# LTC2949.net
KiCad netlist of a schematic drawn in Altium Designer
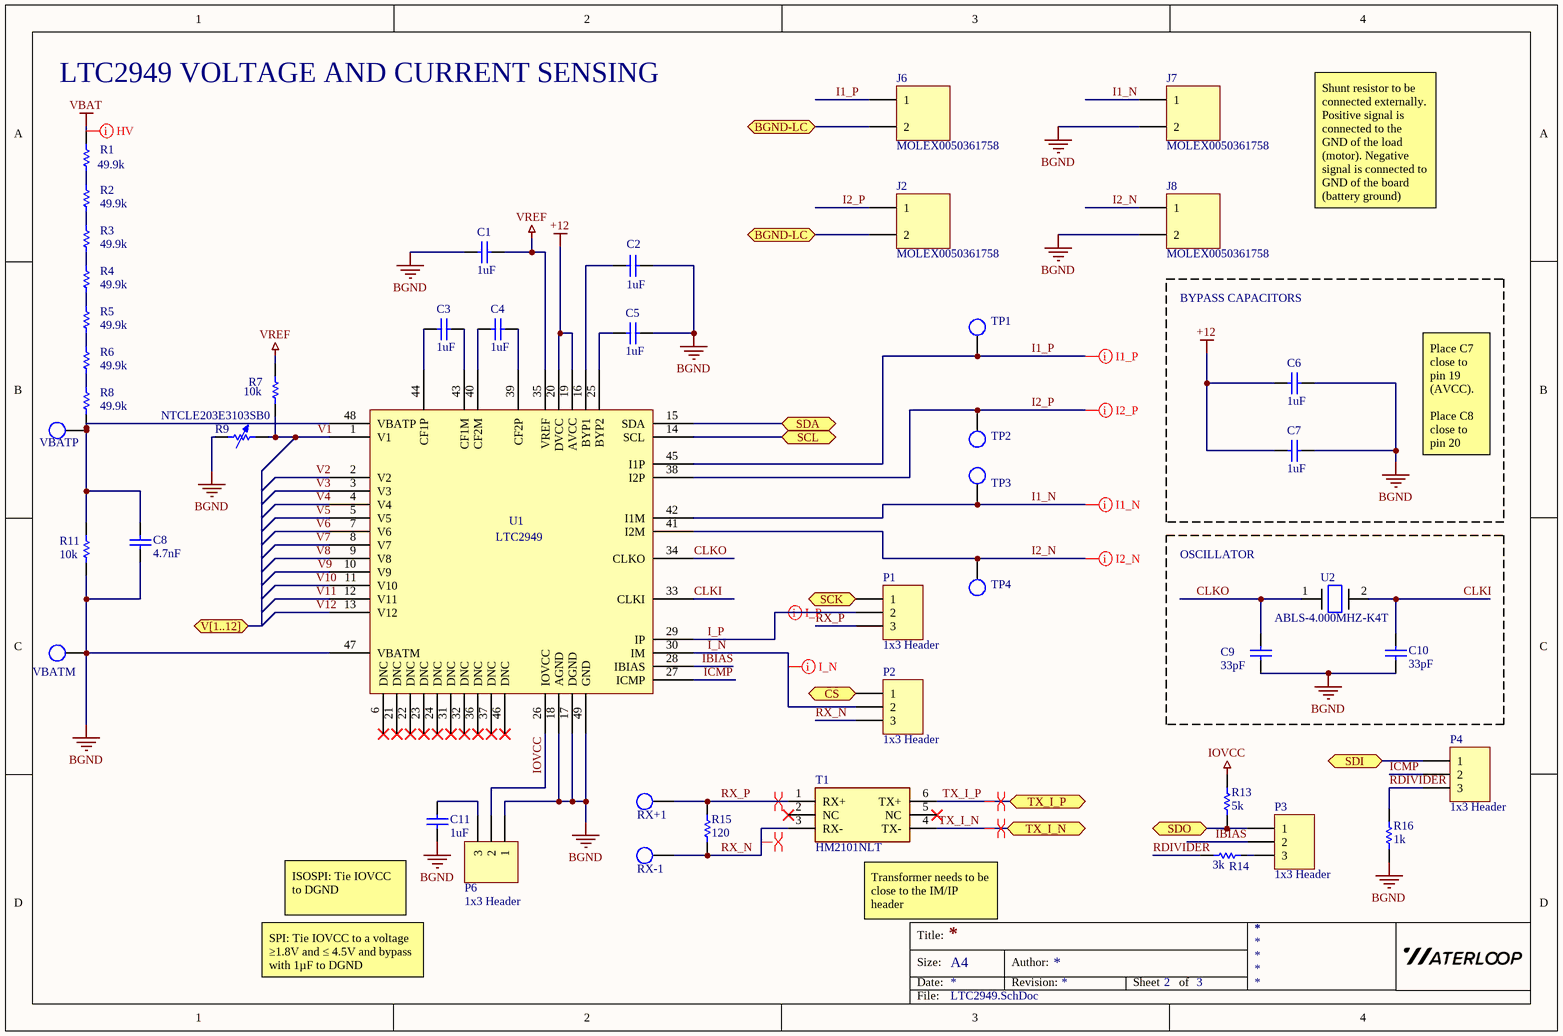
[diagram p0: LTC2949.SchDoc]

(export (version "E")
  (design (tool "Eeschema 10.0.6"))
  (components
    (comp (ref "C1")
      (value "1uF")
      (footprint "0805 - Capacitor")
      (description "Nonpolarized Capacitor")
      (fields (field (name "Comment") "Capacitor - Nonpolarized"))
      (libsource (lib "General") (part "Capacitor - Nonpolarized"))
    )
    (comp (ref "C2")
      (value "1uF")
      (footprint "0805 - Capacitor")
      (description "Nonpolarized Capacitor")
      (libsource (lib "General") (part "Capacitor - Nonpolarized"))
    )
    (comp (ref "C3")
      (value "1uF")
      (footprint "0805 - Capacitor")
      (description "Nonpolarized Capacitor")
      (libsource (lib "General") (part "Capacitor - Nonpolarized"))
    )
    (comp (ref "C4")
      (value "1uF")
      (footprint "0805 - Capacitor")
      (description "Nonpolarized Capacitor")
      (libsource (lib "General") (part "Capacitor - Nonpolarized"))
    )
    (comp (ref "C5")
      (value "1uF")
      (footprint "0805 - Capacitor")
      (description "Nonpolarized Capacitor")
      (libsource (lib "General") (part "Capacitor - Nonpolarized"))
    )
    (comp (ref "C6")
      (value "1uF")
      (footprint "0805 - Capacitor")
      (description "Nonpolarized Capacitor")
      (libsource (lib "General") (part "Capacitor - Nonpolarized"))
    )
    (comp (ref "C7")
      (value "1uF")
      (footprint "0805 - Capacitor")
      (description "Nonpolarized Capacitor")
      (libsource (lib "General") (part "Capacitor - Nonpolarized"))
    )
    (comp (ref "C8")
      (value "4.7nF")
      (footprint "0805 - Capacitor")
      (description "Nonpolarized Capacitor")
      (libsource (lib "General") (part "Capacitor - Nonpolarized"))
    )
    (comp (ref "C9")
      (value "33pF")
      (footprint "0805 - Capacitor")
      (description "Nonpolarized Capacitor")
      (libsource (lib "General") (part "Capacitor - Nonpolarized"))
    )
    (comp (ref "C10")
      (value "33pF")
      (footprint "0805 - Capacitor")
      (description "Nonpolarized Capacitor")
      (libsource (lib "General") (part "Capacitor - Nonpolarized"))
    )
    (comp (ref "C11")
      (value "1uF")
      (footprint "0805 - Capacitor")
      (description "Nonpolarized Capacitor")
      (libsource (lib "General") (part "Capacitor - Nonpolarized"))
    )
    (comp (ref "J2")
      (value "MOLEX0050361758")
      (footprint "Molex0050361758")
      (description "Connector Header Through Hole, Right Angle 2 position -")
      (fields (field (name "MANUFACTURER") "Molex") (field (name "MANUFACTURER PART NUMBER") "0050361758"))
      (libsource (lib "GeneralConnectors") (part "MOLEX0050361758"))
    )
    (comp (ref "J6")
      (value "MOLEX0050361758")
      (footprint "Molex0050361758")
      (description "Connector Header Through Hole, Right Angle 2 position -")
      (fields (field (name "MANUFACTURER") "Molex") (field (name "MANUFACTURER PART NUMBER") "0050361758"))
      (libsource (lib "GeneralConnectors") (part "MOLEX0050361758"))
    )
    (comp (ref "J7")
      (value "MOLEX0050361758")
      (footprint "Molex0050361758")
      (description "Connector Header Through Hole, Right Angle 2 position -")
      (fields (field (name "MANUFACTURER") "Molex") (field (name "MANUFACTURER PART NUMBER") "0050361758"))
      (libsource (lib "GeneralConnectors") (part "MOLEX0050361758"))
    )
    (comp (ref "J8")
      (value "MOLEX0050361758")
      (footprint "Molex0050361758")
      (description "Connector Header Through Hole, Right Angle 2 position -")
      (fields (field (name "MANUFACTURER") "Molex") (field (name "MANUFACTURER PART NUMBER") "0050361758"))
      (libsource (lib "GeneralConnectors") (part "MOLEX0050361758"))
    )
    (comp (ref "P1")
      (value "1x3 Header")
      (footprint "HDR1X3")
      (description "1x3 Pin Header")
      (libsource (lib "GeneralConnectors") (part "1x3 Header"))
    )
    (comp (ref "P2")
      (value "1x3 Header")
      (footprint "HDR1X3")
      (description "1x3 Pin Header")
      (libsource (lib "GeneralConnectors") (part "1x3 Header"))
    )
    (comp (ref "P3")
      (value "1x3 Header")
      (footprint "HDR1X3")
      (description "1x3 Pin Header")
      (libsource (lib "GeneralConnectors") (part "1x3 Header"))
    )
    (comp (ref "P4")
      (value "1x3 Header")
      (footprint "HDR1X3")
      (description "1x3 Pin Header")
      (libsource (lib "GeneralConnectors") (part "1x3 Header"))
    )
    (comp (ref "P6")
      (value "1x3 Header")
      (footprint "HDR1X3")
      (description "1x3 Pin Header")
      (libsource (lib "") (part "1x3 Header_1"))
    )
    (comp (ref "R1")
      (value "49.9k")
      (footprint "1206 - Resistor")
      (description "Resistor")
      (libsource (lib "General") (part "Resistor"))
    )
    (comp (ref "R2")
      (value "49.9k")
      (footprint "1206 - Resistor")
      (description "Resistor")
      (libsource (lib "General") (part "Resistor"))
    )
    (comp (ref "R3")
      (value "49.9k")
      (footprint "1206 - Resistor")
      (description "Resistor")
      (libsource (lib "General") (part "Resistor"))
    )
    (comp (ref "R4")
      (value "49.9k")
      (footprint "1206 - Resistor")
      (description "Resistor")
      (libsource (lib "General") (part "Resistor"))
    )
    (comp (ref "R5")
      (value "49.9k")
      (footprint "1206 - Resistor")
      (description "Resistor")
      (libsource (lib "General") (part "Resistor"))
    )
    (comp (ref "R6")
      (value "49.9k")
      (footprint "1206 - Resistor")
      (description "Resistor")
      (libsource (lib "General") (part "Resistor"))
    )
    (comp (ref "R7")
      (value "10k")
      (footprint "0603 - Resistor")
      (description "Resistor")
      (libsource (lib "General") (part "Resistor"))
    )
    (comp (ref "R8")
      (value "49.9k")
      (footprint "1206 - Resistor")
      (description "Resistor")
      (libsource (lib "General") (part "Resistor"))
    )
    (comp (ref "R9")
      (value "Resistor - Variable")
      (footprint "0603 - Resistor")
      (description "Variable Resistor")
      (libsource (lib "General") (part "Resistor - Variable"))
    )
    (comp (ref "R11")
      (value "10k")
      (footprint "0603 - Resistor")
      (description "Resistor")
      (libsource (lib "General") (part "Resistor"))
    )
    (comp (ref "R13")
      (value "5k")
      (footprint "0603 - Resistor")
      (description "Resistor")
      (libsource (lib "General") (part "Resistor"))
    )
    (comp (ref "R14")
      (value "3k")
      (footprint "0603 - Resistor")
      (description "Resistor")
      (libsource (lib "General") (part "Resistor"))
    )
    (comp (ref "R15")
      (value "120")
      (footprint "0603 - Resistor")
      (description "Resistor")
      (libsource (lib "General") (part "Resistor"))
    )
    (comp (ref "R16")
      (value "1k")
      (footprint "0603 - Resistor")
      (description "Resistor")
      (libsource (lib "General") (part "Resistor"))
    )
    (comp (ref "RX+1")
      (value "Test Point")
      (footprint "Test Point - 5002")
      (libsource (lib "General") (part "Test Point"))
    )
    (comp (ref "RX-1")
      (value "Test Point")
      (footprint "Test Point - 5002")
      (libsource (lib "General") (part "Test Point"))
    )
    (comp (ref "T1")
      (value "HM2101NLT")
      (footprint "HM2101NLT")
      (description "Pulse Transformer 1:1 Surface Mount 150µH, 450µH")
      (libsource (lib "GeneralComponents") (part "HM2101NLT"))
    )
    (comp (ref "TP1")
      (value "Test Point")
      (footprint "Test Point - 5002")
      (libsource (lib "General") (part "Test Point"))
    )
    (comp (ref "TP2")
      (value "Test Point")
      (footprint "Test Point - 5002")
      (libsource (lib "General") (part "Test Point"))
    )
    (comp (ref "TP3")
      (value "Test Point")
      (footprint "Test Point - 5002")
      (libsource (lib "General") (part "Test Point"))
    )
    (comp (ref "TP4")
      (value "Test Point")
      (footprint "Test Point - 5002")
      (libsource (lib "General") (part "Test Point"))
    )
    (comp (ref "U1")
      (value "LTC2949")
      (footprint "LTC2949")
      (fields
        (field (name "MANUFACTURER") "Analog Devices")
        (field (name "MANUFACTURER PART NUMBER") "LTC2949ILXE#3ZZPBF")
      )
      (libsource (lib "BMS") (part "LTC2949"))
    )
    (comp (ref "U2")
      (value "ABLS-4.000MHZ-K4T")
      (footprint "ABLS_4MHZ-K4T")
      (description "Crystal Oscillator 4MHz 18pF")
      (libsource (lib "BMS") (part "ABLS-4.000MHZ-K4T"))
    )
    (comp (ref "VBATM")
      (value "Test Point")
      (footprint "Test Point - 5002")
      (libsource (lib "General") (part "Test Point"))
    )
    (comp (ref "VBATP")
      (value "Test Point")
      (footprint "Test Point - 5002")
      (libsource (lib "General") (part "Test Point"))
    )
  )
  (nets
    (net (code "1") (name "+12") (class "Default")
      (node (ref "C6") (pin "1") (pinfunction "1_1") (pintype "passive"))
      (node (ref "C7") (pin "1") (pinfunction "1_1") (pintype "passive"))
      (node (ref "U1") (pin "19") (pinfunction "AVCC_19") (pintype "power_in"))
      (node (ref "U1") (pin "20") (pinfunction "DVCC_20") (pintype "power_in"))
    )
    (net (code "3") (name "/BGND-LC") (class "Default")
      (node (ref "J2") (pin "2") (pinfunction "2_2") (pintype "passive"))
      (node (ref "J6") (pin "2") (pinfunction "2_2") (pintype "passive"))
    )
    (net (code "4") (name "/CLKI") (class "Default")
      (node (ref "C10") (pin "2") (pinfunction "2_2") (pintype "passive"))
      (node (ref "U1") (pin "33") (pinfunction "CLKI_33") (pintype "passive"))
      (node (ref "U2") (pin "2") (pinfunction "2_2") (pintype "passive"))
    )
    (net (code "5") (name "/CLKO") (class "Default")
      (node (ref "C9") (pin "2") (pinfunction "2_2") (pintype "passive"))
      (node (ref "U1") (pin "34") (pinfunction "CLKO_34") (pintype "passive"))
      (node (ref "U2") (pin "1") (pinfunction "1_1") (pintype "passive"))
    )
    (net (code "6") (name "/CS") (class "Default")
      (node (ref "P2") (pin "1") (pinfunction "1_1") (pintype "passive"))
    )
    (net (code "7") (name "/I1_N") (class "Default")
      (node (ref "J7") (pin "1") (pinfunction "1_1") (pintype "passive"))
      (node (ref "TP3") (pin "1") (pinfunction "0_1") (pintype "passive"))
      (node (ref "U1") (pin "42") (pinfunction "I1M_42") (pintype "passive"))
    )
    (net (code "8") (name "/I1_P") (class "Default")
      (node (ref "J6") (pin "1") (pinfunction "1_1") (pintype "passive"))
      (node (ref "TP1") (pin "1") (pinfunction "0_1") (pintype "passive"))
      (node (ref "U1") (pin "45") (pinfunction "I1P_45") (pintype "passive"))
    )
    (net (code "9") (name "/I2_N") (class "Default")
      (node (ref "J8") (pin "1") (pinfunction "1_1") (pintype "passive"))
      (node (ref "TP4") (pin "1") (pinfunction "0_1") (pintype "passive"))
      (node (ref "U1") (pin "41") (pinfunction "I2M_41") (pintype "passive"))
    )
    (net (code "10") (name "/I2_P") (class "Default")
      (node (ref "J2") (pin "1") (pinfunction "1_1") (pintype "passive"))
      (node (ref "TP2") (pin "1") (pinfunction "0_1") (pintype "passive"))
      (node (ref "U1") (pin "38") (pinfunction "I2P_38") (pintype "passive"))
    )
    (net (code "11") (name "/IBIAS") (class "Default")
      (node (ref "P3") (pin "2") (pinfunction "2_2") (pintype "passive"))
      (node (ref "U1") (pin "28") (pinfunction "IBIAS_28") (pintype "passive"))
    )
    (net (code "12") (name "/ICMP") (class "Default")
      (node (ref "P4") (pin "2") (pinfunction "2_2") (pintype "passive"))
      (node (ref "U1") (pin "27") (pinfunction "ICMP_27") (pintype "passive"))
    )
    (net (code "13") (name "/I_N") (class "Default")
      (node (ref "P2") (pin "2") (pinfunction "2_2") (pintype "passive"))
      (node (ref "U1") (pin "30") (pinfunction "IM_30") (pintype "passive"))
    )
    (net (code "14") (name "/I_P") (class "Default")
      (node (ref "P1") (pin "2") (pinfunction "2_2") (pintype "passive"))
      (node (ref "U1") (pin "29") (pinfunction "IP_29") (pintype "passive"))
    )
    (net (code "15") (name "/RDIVIDER") (class "Default")
      (node (ref "P4") (pin "3") (pinfunction "3_3") (pintype "passive"))
      (node (ref "R14") (pin "1") (pinfunction "1_1") (pintype "passive"))
      (node (ref "R16") (pin "1") (pinfunction "1_1") (pintype "passive"))
    )
    (net (code "16") (name "/RX_N") (class "Default")
      (node (ref "P2") (pin "3") (pinfunction "3_3") (pintype "passive"))
      (node (ref "R15") (pin "1") (pinfunction "1_1") (pintype "passive"))
      (node (ref "RX-1") (pin "1") (pinfunction "0_1") (pintype "passive"))
      (node (ref "T1") (pin "3") (pinfunction "RX-_3") (pintype "passive"))
    )
    (net (code "17") (name "/RX_P") (class "Default")
      (node (ref "P1") (pin "3") (pinfunction "3_3") (pintype "passive"))
      (node (ref "R15") (pin "2") (pinfunction "2_2") (pintype "passive"))
      (node (ref "RX+1") (pin "1") (pinfunction "0_1") (pintype "passive"))
      (node (ref "T1") (pin "1") (pinfunction "RX+_1") (pintype "passive"))
    )
    (net (code "18") (name "/SCK") (class "Default")
      (node (ref "P1") (pin "1") (pinfunction "1_1") (pintype "passive"))
    )
    (net (code "19") (name "/SCL") (class "Default")
      (node (ref "U1") (pin "14") (pinfunction "SCL_14") (pintype "passive"))
    )
    (net (code "20") (name "/SDA") (class "Default")
      (node (ref "U1") (pin "15") (pinfunction "SDA_15") (pintype "passive"))
    )
    (net (code "21") (name "/SDI") (class "Default")
      (node (ref "P4") (pin "1") (pinfunction "1_1") (pintype "passive"))
    )
    (net (code "22") (name "/SDO") (class "Default")
      (node (ref "P3") (pin "1") (pinfunction "1_1") (pintype "passive"))
      (node (ref "R13") (pin "1") (pinfunction "1_1") (pintype "passive"))
    )
    (net (code "23") (name "/TX_I_N") (class "Default")
      (node (ref "T1") (pin "4") (pinfunction "TX-_4") (pintype "passive"))
    )
    (net (code "24") (name "/TX_I_P") (class "Default")
      (node (ref "T1") (pin "6") (pinfunction "TX+_6") (pintype "passive"))
    )
    (net (code "25") (name "/V1") (class "Default")
      (node (ref "R7") (pin "1") (pinfunction "1_1") (pintype "passive"))
      (node (ref "R9") (pin "2") (pinfunction "2_2") (pintype "passive"))
      (node (ref "U1") (pin "1") (pinfunction "V1_1") (pintype "passive"))
    )
    (net (code "26") (name "/V2") (class "Default")
      (node (ref "U1") (pin "2") (pinfunction "V2_2") (pintype "passive"))
    )
    (net (code "27") (name "/V3") (class "Default")
      (node (ref "U1") (pin "3") (pinfunction "V3_3") (pintype "passive"))
    )
    (net (code "28") (name "/V4") (class "Default")
      (node (ref "U1") (pin "4") (pinfunction "V4_4") (pintype "passive"))
    )
    (net (code "29") (name "/V5") (class "Default")
      (node (ref "U1") (pin "5") (pinfunction "V5_5") (pintype "passive"))
    )
    (net (code "30") (name "/V6") (class "Default")
      (node (ref "U1") (pin "7") (pinfunction "V6_7") (pintype "passive"))
    )
    (net (code "31") (name "/V7") (class "Default")
      (node (ref "U1") (pin "8") (pinfunction "V7_8") (pintype "passive"))
    )
    (net (code "32") (name "/V8") (class "Default")
      (node (ref "U1") (pin "9") (pinfunction "V8_9") (pintype "passive"))
    )
    (net (code "33") (name "/V9") (class "Default")
      (node (ref "U1") (pin "10") (pinfunction "V9_10") (pintype "passive"))
    )
    (net (code "34") (name "/V10") (class "Default")
      (node (ref "U1") (pin "11") (pinfunction "V10_11") (pintype "passive"))
    )
    (net (code "35") (name "/V11") (class "Default")
      (node (ref "U1") (pin "12") (pinfunction "V11_12") (pintype "passive"))
    )
    (net (code "36") (name "/V12") (class "Default")
      (node (ref "U1") (pin "13") (pinfunction "V12_13") (pintype "passive"))
    )
    (net (code "38") (name "BGND") (class "Default")
      (node (ref "C1") (pin "1") (pinfunction "1_1") (pintype "passive"))
      (node (ref "C10") (pin "1") (pinfunction "1_1") (pintype "passive"))
      (node (ref "C11") (pin "1") (pinfunction "1_1") (pintype "passive"))
      (node (ref "C2") (pin "2") (pinfunction "2_2") (pintype "passive"))
      (node (ref "C5") (pin "2") (pinfunction "2_2") (pintype "passive"))
      (node (ref "C6") (pin "2") (pinfunction "2_2") (pintype "passive"))
      (node (ref "C7") (pin "2") (pinfunction "2_2") (pintype "passive"))
      (node (ref "C8") (pin "1") (pinfunction "1_1") (pintype "passive"))
      (node (ref "C9") (pin "1") (pinfunction "1_1") (pintype "passive"))
      (node (ref "J7") (pin "2") (pinfunction "2_2") (pintype "passive"))
      (node (ref "J8") (pin "2") (pinfunction "2_2") (pintype "passive"))
      (node (ref "P6") (pin "1") (pinfunction "1_1") (pintype "passive"))
      (node (ref "R11") (pin "1") (pinfunction "1_1") (pintype "passive"))
      (node (ref "R16") (pin "2") (pinfunction "2_2") (pintype "passive"))
      (node (ref "R9") (pin "1") (pinfunction "1_1") (pintype "passive"))
      (node (ref "U1") (pin "17") (pinfunction "DGND_17") (pintype "power_in"))
      (node (ref "U1") (pin "18") (pinfunction "AGND_18") (pintype "power_in"))
      (node (ref "U1") (pin "47") (pinfunction "VBATM_47") (pintype "passive"))
      (node (ref "U1") (pin "49") (pinfunction "GND_49") (pintype "power_in"))
      (node (ref "VBATM") (pin "1") (pinfunction "0_1") (pintype "passive"))
    )
    (net (code "39") (name "IOVCC") (class "Default")
      (node (ref "P6") (pin "2") (pinfunction "2_2") (pintype "passive"))
      (node (ref "R13") (pin "2") (pinfunction "2_2") (pintype "passive"))
      (node (ref "U1") (pin "26") (pinfunction "IOVCC_26") (pintype "power_in"))
    )
    (net (code "40") (name "Net-(C11-Pad2)") (class "Default")
      (node (ref "C11") (pin "2") (pinfunction "2_2") (pintype "passive"))
      (node (ref "P6") (pin "3") (pinfunction "3_3") (pintype "passive"))
    )
    (net (code "41") (name "Net-(P3-Pad3)") (class "Default")
      (node (ref "P3") (pin "3") (pinfunction "3_3") (pintype "passive"))
      (node (ref "R14") (pin "2") (pinfunction "2_2") (pintype "passive"))
    )
    (net (code "42") (name "Net-(R1-Pad1)") (class "Default")
      (node (ref "R1") (pin "1") (pinfunction "1_1") (pintype "passive"))
      (node (ref "R2") (pin "2") (pinfunction "2_2") (pintype "passive"))
    )
    (net (code "43") (name "Net-(R2-Pad1)") (class "Default")
      (node (ref "R2") (pin "1") (pinfunction "1_1") (pintype "passive"))
      (node (ref "R3") (pin "2") (pinfunction "2_2") (pintype "passive"))
    )
    (net (code "44") (name "Net-(R3-Pad1)") (class "Default")
      (node (ref "R3") (pin "1") (pinfunction "1_1") (pintype "passive"))
      (node (ref "R4") (pin "2") (pinfunction "2_2") (pintype "passive"))
    )
    (net (code "45") (name "Net-(R4-Pad1)") (class "Default")
      (node (ref "R4") (pin "1") (pinfunction "1_1") (pintype "passive"))
      (node (ref "R5") (pin "2") (pinfunction "2_2") (pintype "passive"))
    )
    (net (code "46") (name "Net-(R5-Pad1)") (class "Default")
      (node (ref "R5") (pin "1") (pinfunction "1_1") (pintype "passive"))
      (node (ref "R6") (pin "2") (pinfunction "2_2") (pintype "passive"))
    )
    (net (code "47") (name "Net-(R6-Pad1)") (class "Default")
      (node (ref "R6") (pin "1") (pinfunction "1_1") (pintype "passive"))
      (node (ref "R8") (pin "2") (pinfunction "2_2") (pintype "passive"))
    )
    (net (code "48") (name "Net-(U1-BYP1)") (class "Default")
      (node (ref "C2") (pin "1") (pinfunction "1_1") (pintype "passive"))
      (node (ref "U1") (pin "16") (pinfunction "BYP1_16") (pintype "power_in"))
    )
    (net (code "49") (name "Net-(U1-BYP2)") (class "Default")
      (node (ref "C5") (pin "1") (pinfunction "1_1") (pintype "passive"))
      (node (ref "U1") (pin "25") (pinfunction "BYP2_25") (pintype "power_in"))
    )
    (net (code "50") (name "Net-(U1-CF1M)") (class "Default")
      (node (ref "C3") (pin "2") (pinfunction "2_2") (pintype "passive"))
      (node (ref "U1") (pin "43") (pinfunction "CF1M_43") (pintype "passive"))
    )
    (net (code "51") (name "Net-(U1-CF1P)") (class "Default")
      (node (ref "C3") (pin "1") (pinfunction "1_1") (pintype "passive"))
      (node (ref "U1") (pin "44") (pinfunction "CF1P_44") (pintype "passive"))
    )
    (net (code "52") (name "Net-(U1-CF2M)") (class "Default")
      (node (ref "C4") (pin "1") (pinfunction "1_1") (pintype "passive"))
      (node (ref "U1") (pin "40") (pinfunction "CF2M_40") (pintype "passive"))
    )
    (net (code "53") (name "Net-(U1-CF2P)") (class "Default")
      (node (ref "C4") (pin "2") (pinfunction "2_2") (pintype "passive"))
      (node (ref "U1") (pin "39") (pinfunction "CF2P_39") (pintype "passive"))
    )
    (net (code "54") (name "Net-(U1-VBATP)") (class "Default")
      (node (ref "C8") (pin "2") (pinfunction "2_2") (pintype "passive"))
      (node (ref "R11") (pin "2") (pinfunction "2_2") (pintype "passive"))
      (node (ref "R8") (pin "1") (pinfunction "1_1") (pintype "passive"))
      (node (ref "U1") (pin "48") (pinfunction "VBATP_48") (pintype "passive"))
      (node (ref "VBATP") (pin "1") (pinfunction "0_1") (pintype "passive"))
    )
    (net (code "55") (name "VBAT") (class "Default")
      (node (ref "R1") (pin "2") (pinfunction "2_2") (pintype "passive"))
    )
    (net (code "56") (name "VREF") (class "Default")
      (node (ref "C1") (pin "2") (pinfunction "2_2") (pintype "passive"))
      (node (ref "R7") (pin "2") (pinfunction "2_2") (pintype "passive"))
      (node (ref "U1") (pin "35") (pinfunction "VREF_35") (pintype "power_in"))
    )
    (net (code "57") (name "unconnected-(T1-NC-Pad2)") (class "Default")
      (node (ref "T1") (pin "2") (pinfunction "NC_2") (pintype "passive+no_connect"))
    )
    (net (code "58") (name "unconnected-(T1-NC-Pad5)") (class "Default")
      (node (ref "T1") (pin "5") (pinfunction "NC_5") (pintype "passive+no_connect"))
    )
    (net (code "59") (name "unconnected-(U1-DNC-Pad6)") (class "Default")
      (node (ref "U1") (pin "6") (pinfunction "DNC_6") (pintype "passive+no_connect"))
    )
    (net (code "60") (name "unconnected-(U1-DNC-Pad21)") (class "Default")
      (node (ref "U1") (pin "21") (pinfunction "DNC_21") (pintype "passive+no_connect"))
    )
    (net (code "61") (name "unconnected-(U1-DNC-Pad22)") (class "Default")
      (node (ref "U1") (pin "22") (pinfunction "DNC_22") (pintype "passive+no_connect"))
    )
    (net (code "62") (name "unconnected-(U1-DNC-Pad23)") (class "Default")
      (node (ref "U1") (pin "23") (pinfunction "DNC_23") (pintype "passive+no_connect"))
    )
    (net (code "63") (name "unconnected-(U1-DNC-Pad24)") (class "Default")
      (node (ref "U1") (pin "24") (pinfunction "DNC_24") (pintype "passive+no_connect"))
    )
    (net (code "64") (name "unconnected-(U1-DNC-Pad31)") (class "Default")
      (node (ref "U1") (pin "31") (pinfunction "DNC_31") (pintype "passive+no_connect"))
    )
    (net (code "65") (name "unconnected-(U1-DNC-Pad32)") (class "Default")
      (node (ref "U1") (pin "32") (pinfunction "DNC_32") (pintype "passive+no_connect"))
    )
    (net (code "66") (name "unconnected-(U1-DNC-Pad36)") (class "Default")
      (node (ref "U1") (pin "36") (pinfunction "DNC_36") (pintype "passive+no_connect"))
    )
    (net (code "67") (name "unconnected-(U1-DNC-Pad37)") (class "Default")
      (node (ref "U1") (pin "37") (pinfunction "DNC_37") (pintype "passive+no_connect"))
    )
    (net (code "68") (name "unconnected-(U1-DNC-Pad46)") (class "Default")
      (node (ref "U1") (pin "46") (pinfunction "DNC_46") (pintype "passive+no_connect"))
    )
  )
)
